# SHDN-BSPD-S06-V00-IsolatedCAN.net
KiCad netlist of a schematic drawn in Altium Designer
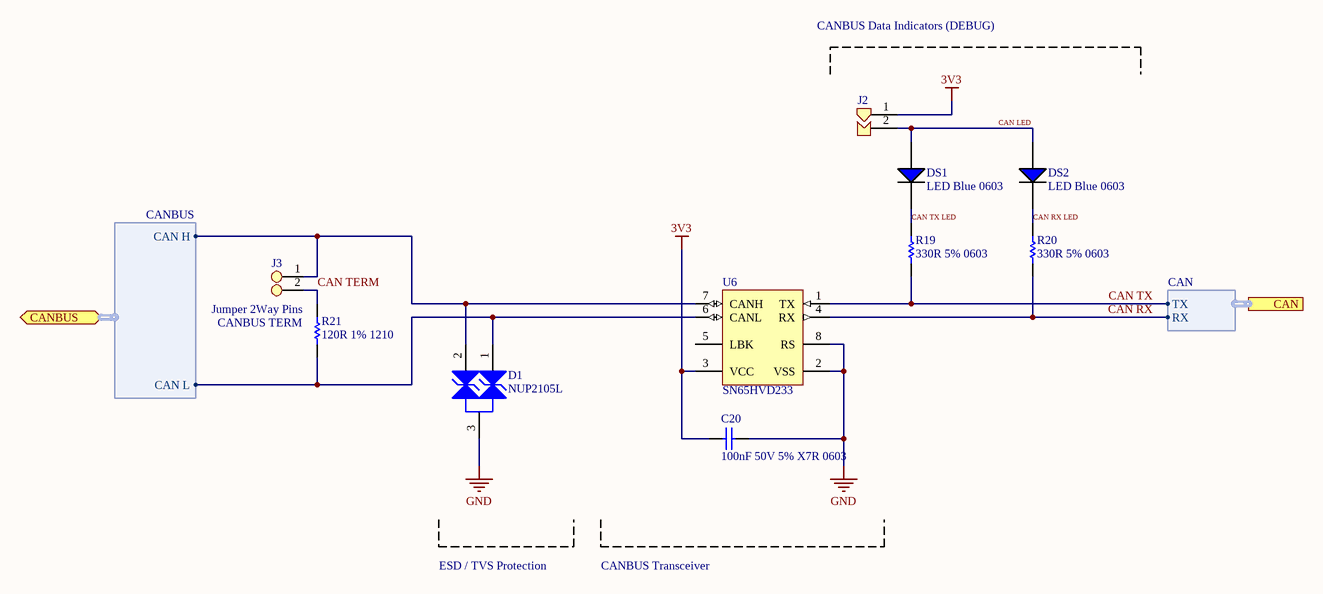
[diagram p0: SHDN-BSPD-S06-V00-IsolatedCAN.SchDoc]

(export (version "E")
  (design (tool "Eeschema 10.0.6"))
  (components
    (comp (ref "C20")
      (value "100nF 50V 5% X7R 0603")
      (footprint "Cap_Ceramic_0603")
      (description "Capacitor, Ceramic, SMD, 100nF, 50V, 5%, X7R, 0603")
      (libsource (lib "StandardCapacitors") (part "100nF 50V 5% X7R 0603"))
    )
    (comp (ref "D1")
      (value "NUP2105L")
      (footprint "NUP2105L")
      (libsource (lib "QUTMS_CANLibrary") (part "NUP2105L"))
    )
    (comp (ref "DS1")
      (value "LED Blue 0603")
      (footprint "LED BLUE 0603")
      (libsource (lib "QUTMS_LEDLibrary") (part "LED Blue 0603"))
    )
    (comp (ref "DS2")
      (value "LED Blue 0603")
      (footprint "LED BLUE 0603")
      (libsource (lib "QUTMS_LEDLibrary") (part "LED Blue 0603"))
    )
    (comp (ref "J2")
      (value "Jumper 2Way Solderable")
      (footprint "Jumper_2Way_Solderable")
      (description "Jumper 2Way Side Solderable")
      (libsource (lib "QUTMS_JumperLibrary") (part "Jumper 2Way Side Solderable"))
    )
    (comp (ref "J3")
      (value "Jumper 2Way Pins")
      (footprint "Jumper_2Way_Pin")
      (description "Jumper 2Way Side Pins")
      (libsource (lib "QUTMS_JumperLibrary") (part "Jumper 2Way Side Pins"))
    )
    (comp (ref "R19")
      (value "330R 5% 0603")
      (footprint "Res_ThinFilm_0603")
      (description "Resistor, SMD, 330R, 0.1W, 5%, 0603")
      (libsource (lib "StandardResistors") (part "330R 5% 0603"))
    )
    (comp (ref "R20")
      (value "330R 5% 0603")
      (footprint "Res_ThinFilm_0603")
      (description "Resistor, SMD, 330R, 0.1W, 5%, 0603")
      (libsource (lib "StandardResistors") (part "330R 5% 0603"))
    )
    (comp (ref "R21")
      (value "120R 1% 1210")
      (footprint "Res_ThinFilm_1210")
      (description "Resistor, SMD, 120R, 0.25W, 1%, 1210")
      (libsource (lib "StandardResistors") (part "120R 1% 1210"))
    )
    (comp (ref "U6")
      (value "SN65HVD233")
      (footprint "SN65HVD233DR")
      (libsource (lib "QUTMS_CANLibrary") (part "SN65HVD233"))
    )
  )
  (nets
    (net (code "3") (name "/CAN LED") (class "Default")
      (node (ref "DS1") (pin "1") (pinfunction "A_1") (pintype "passive"))
      (node (ref "DS2") (pin "1") (pinfunction "A_1") (pintype "passive"))
      (node (ref "J2") (pin "2") (pinfunction "2_2") (pintype "passive"))
    )
    (net (code "4") (name "/CAN RX") (class "Default")
      (node (ref "R20") (pin "1") (pinfunction "1_1") (pintype "passive"))
      (node (ref "U6") (pin "4") (pinfunction "RX_4") (pintype "output"))
    )
    (net (code "5") (name "/CAN RX LED") (class "Default")
      (node (ref "DS2") (pin "2") (pinfunction "C_2") (pintype "passive"))
      (node (ref "R20") (pin "2") (pinfunction "2_2") (pintype "passive"))
    )
    (net (code "6") (name "/CAN TERM") (class "Default")
      (node (ref "J3") (pin "2") (pinfunction "2_2") (pintype "passive"))
      (node (ref "R21") (pin "2") (pinfunction "2_2") (pintype "passive"))
    )
    (net (code "7") (name "/CAN TX") (class "Default")
      (node (ref "R19") (pin "1") (pinfunction "1_1") (pintype "passive"))
      (node (ref "U6") (pin "1") (pinfunction "TX_1") (pintype "input"))
    )
    (net (code "8") (name "/CAN TX LED") (class "Default")
      (node (ref "DS1") (pin "2") (pinfunction "C_2") (pintype "passive"))
      (node (ref "R19") (pin "2") (pinfunction "2_2") (pintype "passive"))
    )
    (net (code "11") (name "3V3") (class "Default")
      (node (ref "C20") (pin "2") (pinfunction "2_2") (pintype "passive"))
      (node (ref "J2") (pin "1") (pinfunction "1_1") (pintype "passive"))
      (node (ref "U6") (pin "3") (pinfunction "VCC_3") (pintype "passive"))
    )
    (net (code "12") (name "GND") (class "Default")
      (node (ref "C20") (pin "1") (pinfunction "1_1") (pintype "passive"))
      (node (ref "D1") (pin "3") (pinfunction "3_3") (pintype "passive"))
      (node (ref "U6") (pin "2") (pinfunction "VSS_2") (pintype "passive"))
      (node (ref "U6") (pin "8") (pinfunction "RS_8") (pintype "passive"))
    )
    (net (code "13") (name "Net-(U6-CANH)") (class "Default")
      (node (ref "D1") (pin "2") (pinfunction "2_2") (pintype "passive"))
      (node (ref "J3") (pin "1") (pinfunction "1_1") (pintype "passive"))
      (node (ref "U6") (pin "7") (pinfunction "CANH_7") (pintype "bidirectional"))
    )
    (net (code "14") (name "Net-(U6-CANL)") (class "Default")
      (node (ref "D1") (pin "1") (pinfunction "1_1") (pintype "passive"))
      (node (ref "R21") (pin "1") (pinfunction "1_1") (pintype "passive"))
      (node (ref "U6") (pin "6") (pinfunction "CANL_6") (pintype "bidirectional"))
    )
    (net (code "15") (name "unconnected-(U6-LBK-Pad5)") (class "Default")
      (node (ref "U6") (pin "5") (pinfunction "LBK_5") (pintype "passive"))
    )
  )
)
